# AD.net
KiCad netlist of a schematic drawn in Altium Designer
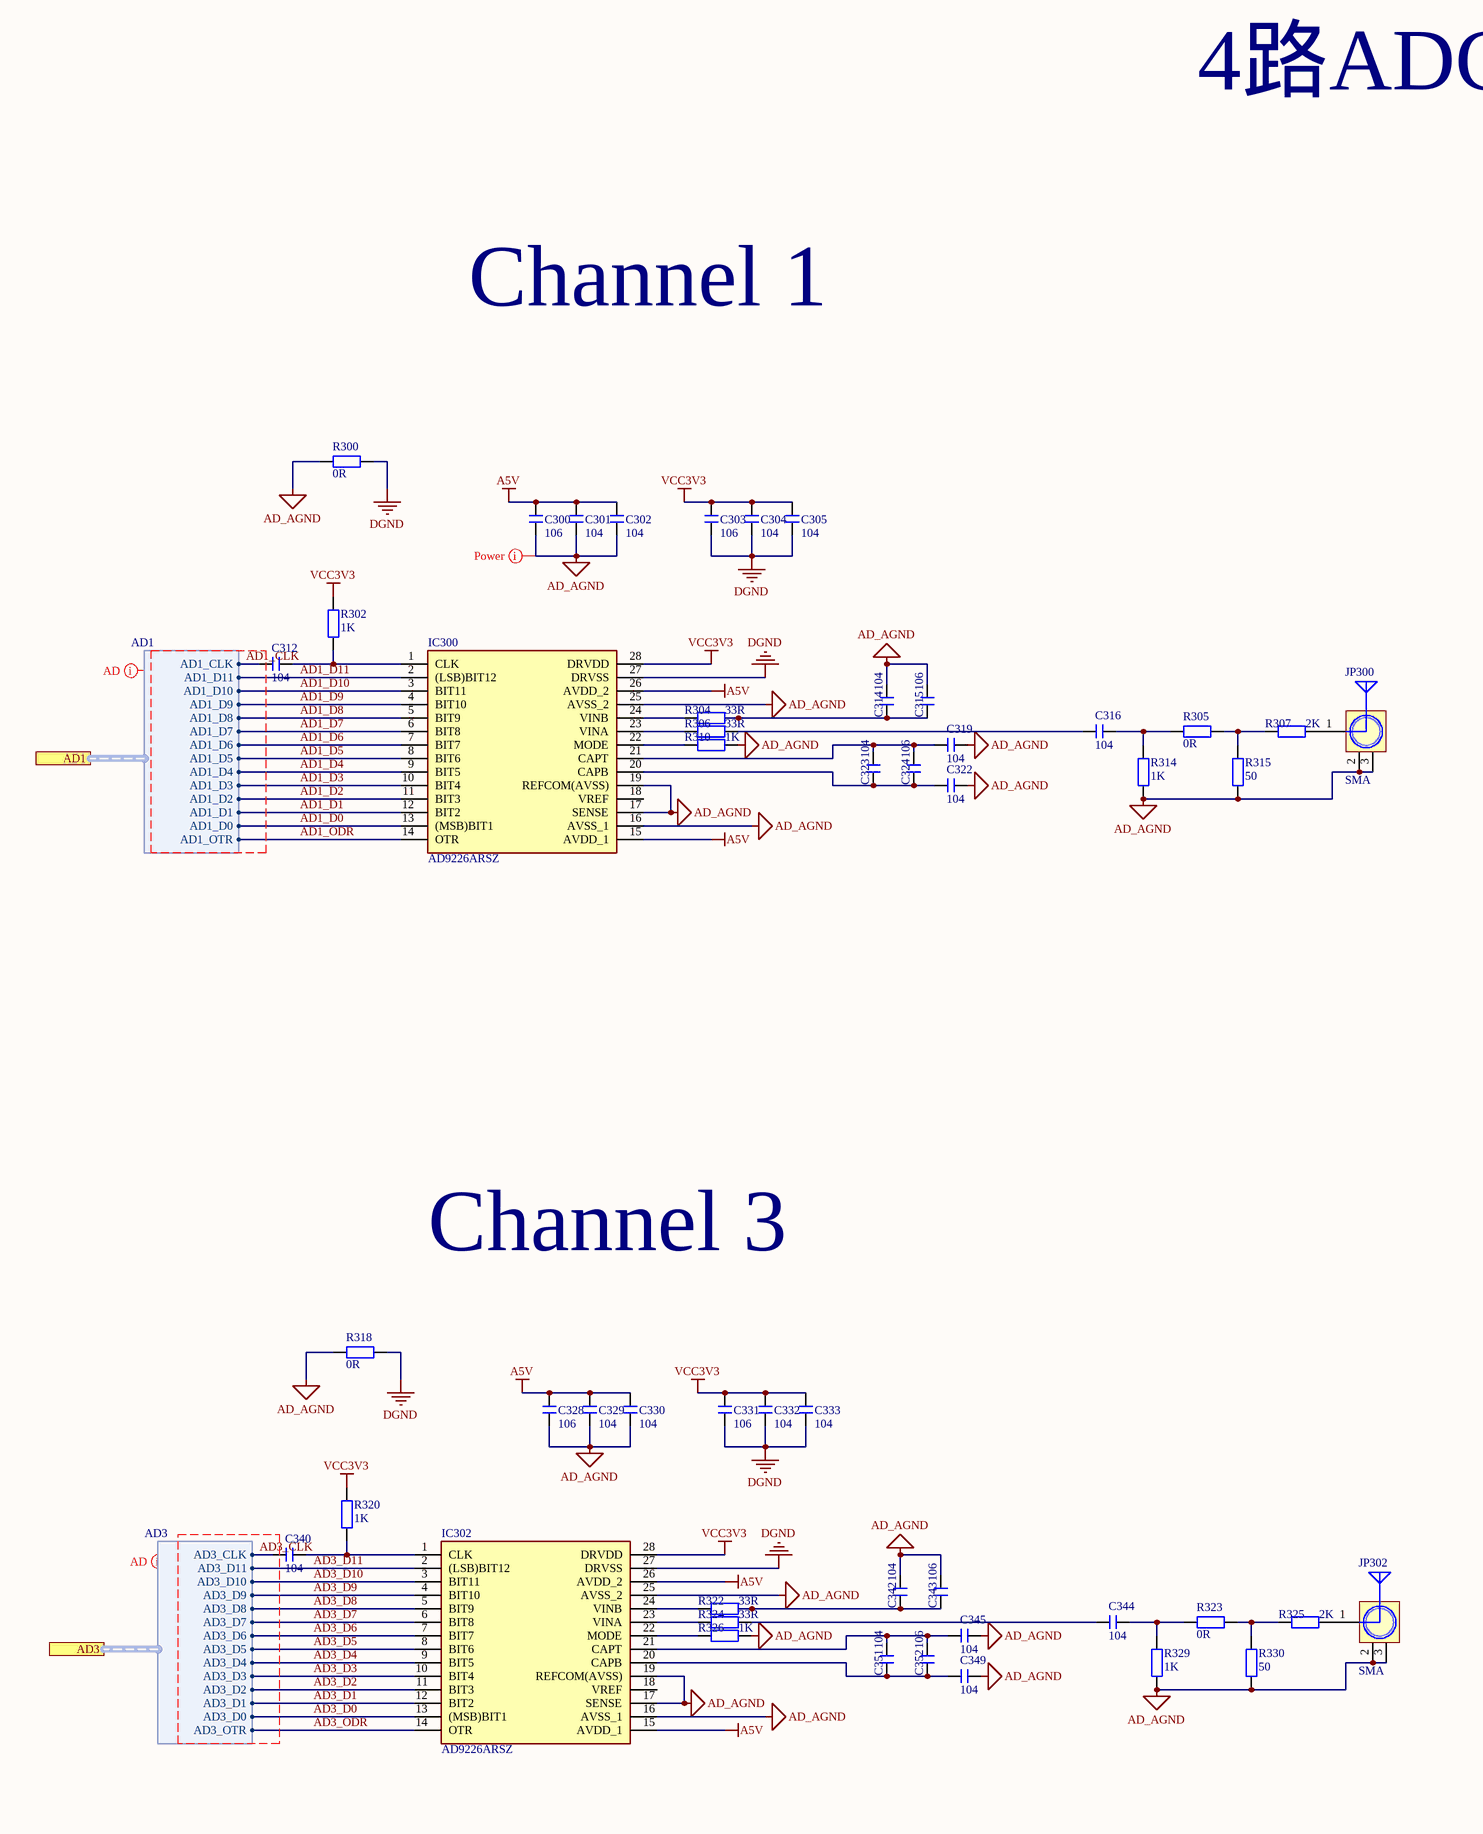
[diagram p0: AD.SchDoc, left]
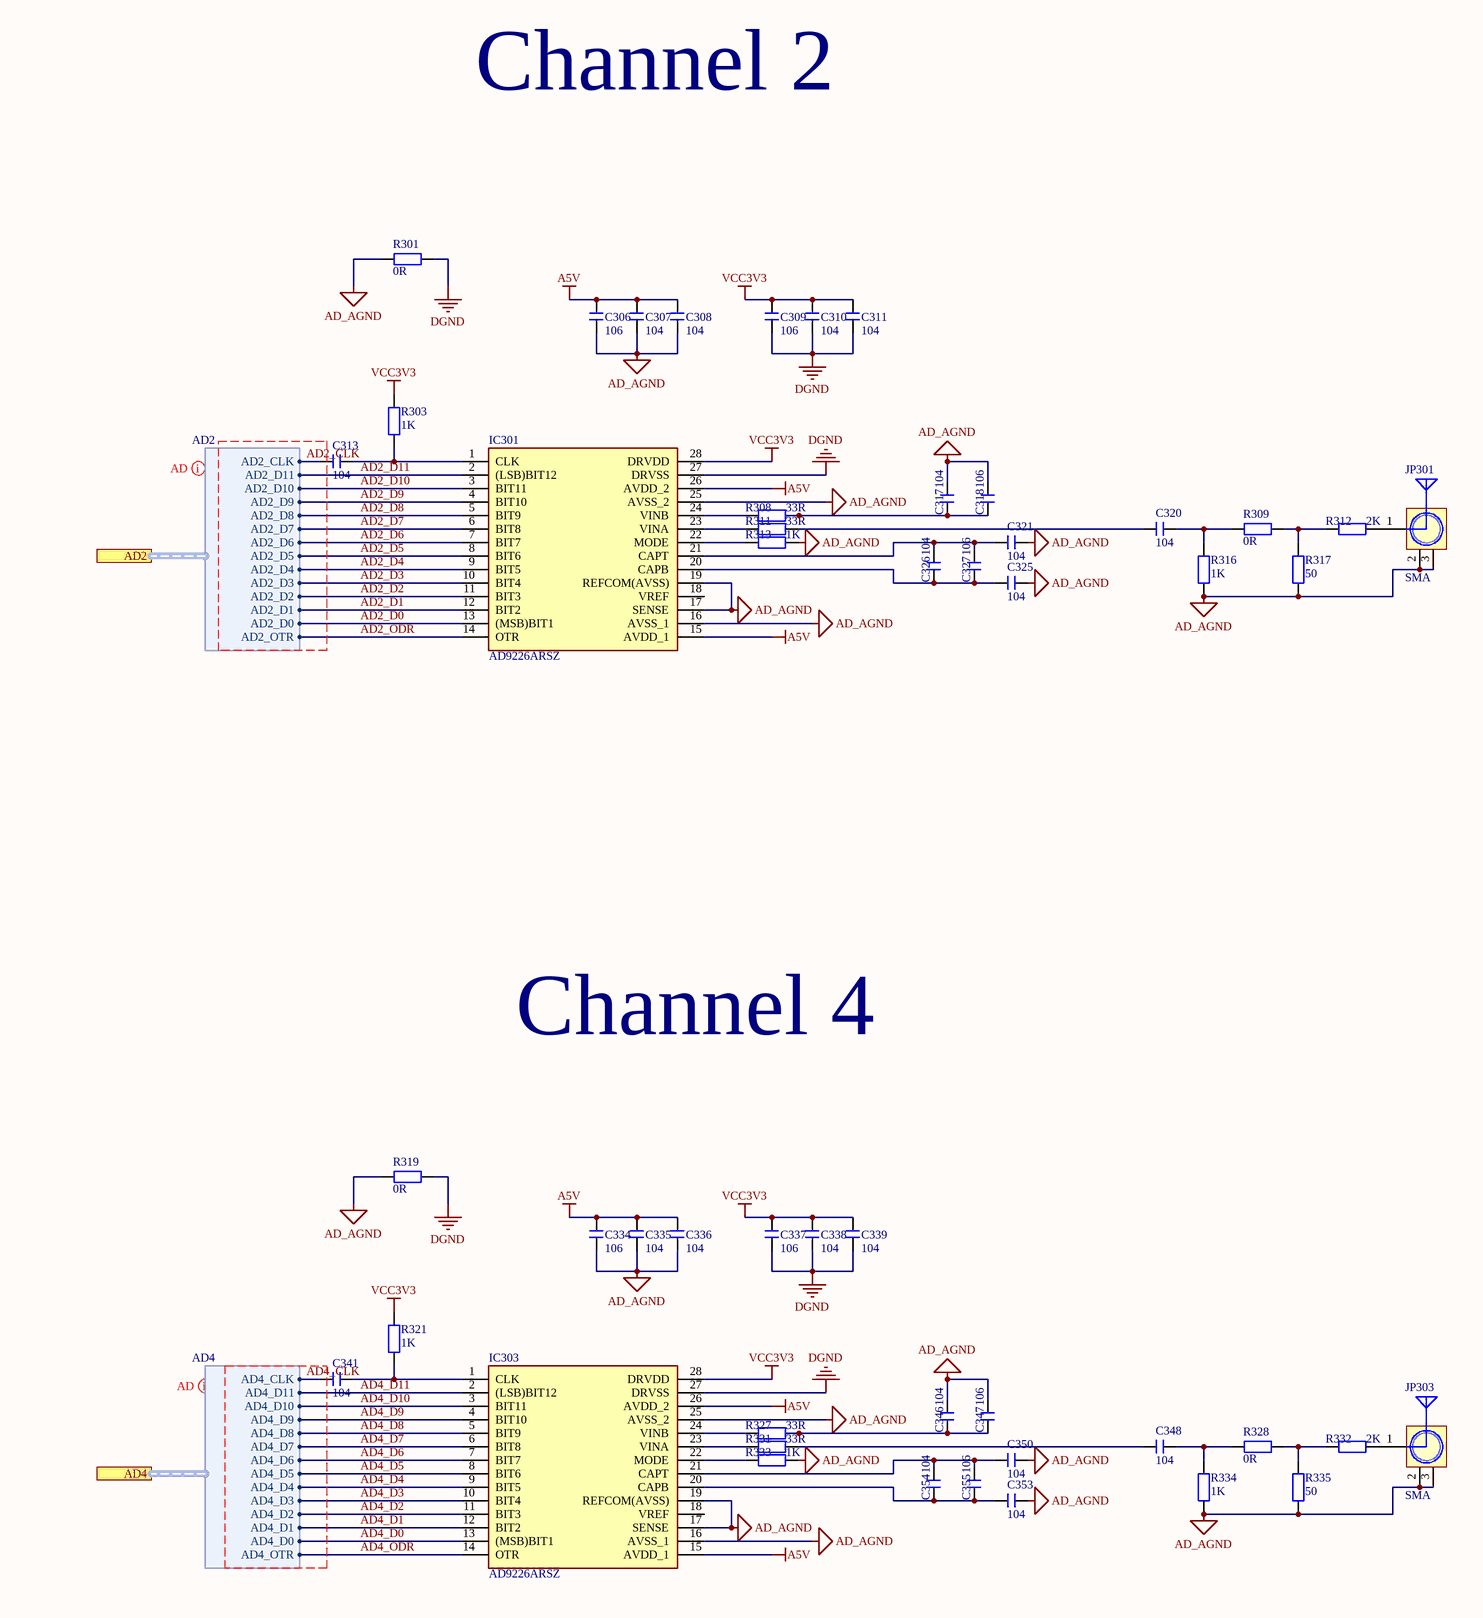
[diagram p1: AD.SchDoc, right]

(export (version "E")
  (design (tool "Eeschema 10.0.6"))
  (components
    (comp (ref "C300")
      (value "106")
      (footprint "C 0402_M")
      (description "无极性贴片电容")
      (fields (field (name "版权归属") "源创客"))
      (libsource (lib "3.1   - 电阻-电容-电感") (part "C"))
    )
    (comp (ref "C301")
      (value "104")
      (footprint "C 0402_M")
      (description "无极性贴片电容")
      (fields (field (name "版权归属") "源创客"))
      (libsource (lib "3.1   - 电阻-电容-电感") (part "C"))
    )
    (comp (ref "C302")
      (value "104")
      (footprint "C 0402_M")
      (description "无极性贴片电容")
      (fields (field (name "版权归属") "源创客"))
      (libsource (lib "3.1   - 电阻-电容-电感") (part "C"))
    )
    (comp (ref "C303")
      (value "106")
      (footprint "C 0402_M")
      (description "无极性贴片电容")
      (fields (field (name "版权归属") "源创客"))
      (libsource (lib "3.1   - 电阻-电容-电感") (part "C"))
    )
    (comp (ref "C304")
      (value "104")
      (footprint "C 0402_M")
      (description "无极性贴片电容")
      (fields (field (name "版权归属") "源创客"))
      (libsource (lib "3.1   - 电阻-电容-电感") (part "C"))
    )
    (comp (ref "C305")
      (value "104")
      (footprint "C 0402_M")
      (description "无极性贴片电容")
      (fields (field (name "版权归属") "源创客"))
      (libsource (lib "3.1   - 电阻-电容-电感") (part "C"))
    )
    (comp (ref "C306")
      (value "106")
      (footprint "C 0402_M")
      (description "无极性贴片电容")
      (fields (field (name "版权归属") "源创客"))
      (libsource (lib "3.1   - 电阻-电容-电感") (part "C"))
    )
    (comp (ref "C307")
      (value "104")
      (footprint "C 0402_M")
      (description "无极性贴片电容")
      (fields (field (name "版权归属") "源创客"))
      (libsource (lib "3.1   - 电阻-电容-电感") (part "C"))
    )
    (comp (ref "C308")
      (value "104")
      (footprint "C 0402_M")
      (description "无极性贴片电容")
      (fields (field (name "版权归属") "源创客"))
      (libsource (lib "3.1   - 电阻-电容-电感") (part "C"))
    )
    (comp (ref "C309")
      (value "106")
      (footprint "C 0402_M")
      (description "无极性贴片电容")
      (fields (field (name "版权归属") "源创客"))
      (libsource (lib "3.1   - 电阻-电容-电感") (part "C"))
    )
    (comp (ref "C310")
      (value "104")
      (footprint "C 0402_M")
      (description "无极性贴片电容")
      (fields (field (name "版权归属") "源创客"))
      (libsource (lib "3.1   - 电阻-电容-电感") (part "C"))
    )
    (comp (ref "C311")
      (value "104")
      (footprint "C 0402_M")
      (description "无极性贴片电容")
      (fields (field (name "版权归属") "源创客"))
      (libsource (lib "3.1   - 电阻-电容-电感") (part "C"))
    )
    (comp (ref "C312")
      (value "104")
      (footprint "C 0402_M")
      (description "无极性贴片电容")
      (fields (field (name "版权归属") "源创客"))
      (libsource (lib "3.1   - 电阻-电容-电感") (part "C"))
    )
    (comp (ref "C313")
      (value "104")
      (footprint "C 0402_M")
      (description "无极性贴片电容")
      (fields (field (name "版权归属") "源创客"))
      (libsource (lib "3.1   - 电阻-电容-电感") (part "C"))
    )
    (comp (ref "C314")
      (value "104")
      (footprint "C 0402_M")
      (description "无极性贴片电容")
      (fields (field (name "版权归属") "源创客"))
      (libsource (lib "3.1   - 电阻-电容-电感") (part "C"))
    )
    (comp (ref "C315")
      (value "106")
      (footprint "C 0402_M")
      (description "无极性贴片电容")
      (fields (field (name "版权归属") "源创客"))
      (libsource (lib "3.1   - 电阻-电容-电感") (part "C"))
    )
    (comp (ref "C316")
      (value "104")
      (footprint "C 0402_M")
      (description "无极性贴片电容")
      (fields (field (name "版权归属") "源创客"))
      (libsource (lib "3.1   - 电阻-电容-电感") (part "C"))
    )
    (comp (ref "C317")
      (value "104")
      (footprint "C 0402_M")
      (description "无极性贴片电容")
      (fields (field (name "版权归属") "源创客"))
      (libsource (lib "3.1   - 电阻-电容-电感") (part "C"))
    )
    (comp (ref "C318")
      (value "106")
      (footprint "C 0402_M")
      (description "无极性贴片电容")
      (fields (field (name "版权归属") "源创客"))
      (libsource (lib "3.1   - 电阻-电容-电感") (part "C"))
    )
    (comp (ref "C319")
      (value "104")
      (footprint "C 0402_M")
      (description "无极性贴片电容")
      (fields (field (name "版权归属") "源创客"))
      (libsource (lib "3.1   - 电阻-电容-电感") (part "C"))
    )
    (comp (ref "C320")
      (value "104")
      (footprint "C 0402_M")
      (description "无极性贴片电容")
      (fields (field (name "版权归属") "源创客"))
      (libsource (lib "3.1   - 电阻-电容-电感") (part "C"))
    )
    (comp (ref "C321")
      (value "104")
      (footprint "C 0402_M")
      (description "无极性贴片电容")
      (fields (field (name "版权归属") "源创客"))
      (libsource (lib "3.1   - 电阻-电容-电感") (part "C"))
    )
    (comp (ref "C322")
      (value "104")
      (footprint "C 0402_M")
      (description "无极性贴片电容")
      (fields (field (name "版权归属") "源创客"))
      (libsource (lib "3.1   - 电阻-电容-电感") (part "C"))
    )
    (comp (ref "C323")
      (value "104")
      (footprint "C 0402_M")
      (description "无极性贴片电容")
      (fields (field (name "版权归属") "源创客"))
      (libsource (lib "3.1   - 电阻-电容-电感") (part "C"))
    )
    (comp (ref "C324")
      (value "106")
      (footprint "C 0402_M")
      (description "无极性贴片电容")
      (fields (field (name "版权归属") "源创客"))
      (libsource (lib "3.1   - 电阻-电容-电感") (part "C"))
    )
    (comp (ref "C325")
      (value "104")
      (footprint "C 0402_M")
      (description "无极性贴片电容")
      (fields (field (name "版权归属") "源创客"))
      (libsource (lib "3.1   - 电阻-电容-电感") (part "C"))
    )
    (comp (ref "C326")
      (value "104")
      (footprint "C 0402_M")
      (description "无极性贴片电容")
      (fields (field (name "版权归属") "源创客"))
      (libsource (lib "3.1   - 电阻-电容-电感") (part "C"))
    )
    (comp (ref "C327")
      (value "106")
      (footprint "C 0402_M")
      (description "无极性贴片电容")
      (fields (field (name "版权归属") "源创客"))
      (libsource (lib "3.1   - 电阻-电容-电感") (part "C"))
    )
    (comp (ref "C328")
      (value "106")
      (footprint "C 0402_M")
      (description "无极性贴片电容")
      (fields (field (name "版权归属") "源创客"))
      (libsource (lib "3.1   - 电阻-电容-电感") (part "C"))
    )
    (comp (ref "C329")
      (value "104")
      (footprint "C 0402_M")
      (description "无极性贴片电容")
      (fields (field (name "版权归属") "源创客"))
      (libsource (lib "3.1   - 电阻-电容-电感") (part "C"))
    )
    (comp (ref "C330")
      (value "104")
      (footprint "C 0402_M")
      (description "无极性贴片电容")
      (fields (field (name "版权归属") "源创客"))
      (libsource (lib "3.1   - 电阻-电容-电感") (part "C"))
    )
    (comp (ref "C331")
      (value "106")
      (footprint "C 0402_M")
      (description "无极性贴片电容")
      (fields (field (name "版权归属") "源创客"))
      (libsource (lib "3.1   - 电阻-电容-电感") (part "C"))
    )
    (comp (ref "C332")
      (value "104")
      (footprint "C 0402_M")
      (description "无极性贴片电容")
      (fields (field (name "版权归属") "源创客"))
      (libsource (lib "3.1   - 电阻-电容-电感") (part "C"))
    )
    (comp (ref "C333")
      (value "104")
      (footprint "C 0402_M")
      (description "无极性贴片电容")
      (fields (field (name "版权归属") "源创客"))
      (libsource (lib "3.1   - 电阻-电容-电感") (part "C"))
    )
    (comp (ref "C334")
      (value "106")
      (footprint "C 0402_M")
      (description "无极性贴片电容")
      (fields (field (name "版权归属") "源创客"))
      (libsource (lib "3.1   - 电阻-电容-电感") (part "C"))
    )
    (comp (ref "C335")
      (value "104")
      (footprint "C 0402_M")
      (description "无极性贴片电容")
      (fields (field (name "版权归属") "源创客"))
      (libsource (lib "3.1   - 电阻-电容-电感") (part "C"))
    )
    (comp (ref "C336")
      (value "104")
      (footprint "C 0402_M")
      (description "无极性贴片电容")
      (fields (field (name "版权归属") "源创客"))
      (libsource (lib "3.1   - 电阻-电容-电感") (part "C"))
    )
    (comp (ref "C337")
      (value "106")
      (footprint "C 0402_M")
      (description "无极性贴片电容")
      (fields (field (name "版权归属") "源创客"))
      (libsource (lib "3.1   - 电阻-电容-电感") (part "C"))
    )
    (comp (ref "C338")
      (value "104")
      (footprint "C 0402_M")
      (description "无极性贴片电容")
      (fields (field (name "版权归属") "源创客"))
      (libsource (lib "3.1   - 电阻-电容-电感") (part "C"))
    )
    (comp (ref "C339")
      (value "104")
      (footprint "C 0402_M")
      (description "无极性贴片电容")
      (fields (field (name "版权归属") "源创客"))
      (libsource (lib "3.1   - 电阻-电容-电感") (part "C"))
    )
    (comp (ref "C340")
      (value "104")
      (footprint "C 0402_M")
      (description "无极性贴片电容")
      (fields (field (name "版权归属") "源创客"))
      (libsource (lib "3.1   - 电阻-电容-电感") (part "C"))
    )
    (comp (ref "C341")
      (value "104")
      (footprint "C 0402_M")
      (description "无极性贴片电容")
      (fields (field (name "版权归属") "源创客"))
      (libsource (lib "3.1   - 电阻-电容-电感") (part "C"))
    )
    (comp (ref "C342")
      (value "104")
      (footprint "C 0402_M")
      (description "无极性贴片电容")
      (fields (field (name "版权归属") "源创客"))
      (libsource (lib "3.1   - 电阻-电容-电感") (part "C"))
    )
    (comp (ref "C343")
      (value "106")
      (footprint "C 0402_M")
      (description "无极性贴片电容")
      (fields (field (name "版权归属") "源创客"))
      (libsource (lib "3.1   - 电阻-电容-电感") (part "C"))
    )
    (comp (ref "C344")
      (value "104")
      (footprint "C 0402_M")
      (description "无极性贴片电容")
      (fields (field (name "版权归属") "源创客"))
      (libsource (lib "3.1   - 电阻-电容-电感") (part "C"))
    )
    (comp (ref "C345")
      (value "104")
      (footprint "C 0402_M")
      (description "无极性贴片电容")
      (fields (field (name "版权归属") "源创客"))
      (libsource (lib "3.1   - 电阻-电容-电感") (part "C"))
    )
    (comp (ref "C346")
      (value "104")
      (footprint "C 0402_M")
      (description "无极性贴片电容")
      (fields (field (name "版权归属") "源创客"))
      (libsource (lib "3.1   - 电阻-电容-电感") (part "C"))
    )
    (comp (ref "C347")
      (value "106")
      (footprint "C 0402_M")
      (description "无极性贴片电容")
      (fields (field (name "版权归属") "源创客"))
      (libsource (lib "3.1   - 电阻-电容-电感") (part "C"))
    )
    (comp (ref "C348")
      (value "104")
      (footprint "C 0402_M")
      (description "无极性贴片电容")
      (fields (field (name "版权归属") "源创客"))
      (libsource (lib "3.1   - 电阻-电容-电感") (part "C"))
    )
    (comp (ref "C349")
      (value "104")
      (footprint "C 0402_M")
      (description "无极性贴片电容")
      (fields (field (name "版权归属") "源创客"))
      (libsource (lib "3.1   - 电阻-电容-电感") (part "C"))
    )
    (comp (ref "C350")
      (value "104")
      (footprint "C 0402_M")
      (description "无极性贴片电容")
      (fields (field (name "版权归属") "源创客"))
      (libsource (lib "3.1   - 电阻-电容-电感") (part "C"))
    )
    (comp (ref "C351")
      (value "104")
      (footprint "C 0402_M")
      (description "无极性贴片电容")
      (fields (field (name "版权归属") "源创客"))
      (libsource (lib "3.1   - 电阻-电容-电感") (part "C"))
    )
    (comp (ref "C352")
      (value "106")
      (footprint "C 0402_M")
      (description "无极性贴片电容")
      (fields (field (name "版权归属") "源创客"))
      (libsource (lib "3.1   - 电阻-电容-电感") (part "C"))
    )
    (comp (ref "C353")
      (value "104")
      (footprint "C 0402_M")
      (description "无极性贴片电容")
      (fields (field (name "版权归属") "源创客"))
      (libsource (lib "3.1   - 电阻-电容-电感") (part "C"))
    )
    (comp (ref "C354")
      (value "104")
      (footprint "C 0402_M")
      (description "无极性贴片电容")
      (fields (field (name "版权归属") "源创客"))
      (libsource (lib "3.1   - 电阻-电容-电感") (part "C"))
    )
    (comp (ref "C355")
      (value "106")
      (footprint "C 0402_M")
      (description "无极性贴片电容")
      (fields (field (name "版权归属") "源创客"))
      (libsource (lib "3.1   - 电阻-电容-电感") (part "C"))
    )
    (comp (ref "IC300")
      (value "AD9226ARSZ")
      (footprint "PcbLib1:SOP65P777X198-28N")
      (description "Integrated Circuit")
      (fields (field (name "MOUSER PART NUMBER") "584-AD9226ARSZ") (field (name "RS PART NUMBER") "4973407P"))
      (libsource (lib "altium-import") (part "root_0_AD9226ARSZ_"))
    )
    (comp (ref "IC301")
      (value "AD9226ARSZ")
      (footprint "PcbLib1:SOP65P777X198-28N")
      (description "Integrated Circuit")
      (fields (field (name "MOUSER PART NUMBER") "584-AD9226ARSZ") (field (name "RS PART NUMBER") "4973407P"))
      (libsource (lib "altium-import") (part "root_0_AD9226ARSZ_"))
    )
    (comp (ref "IC302")
      (value "AD9226ARSZ")
      (footprint "PcbLib1:SOP65P777X198-28N")
      (description "Integrated Circuit")
      (fields (field (name "MOUSER PART NUMBER") "584-AD9226ARSZ") (field (name "RS PART NUMBER") "4973407P"))
      (libsource (lib "altium-import") (part "root_0_AD9226ARSZ_"))
    )
    (comp (ref "IC303")
      (value "AD9226ARSZ")
      (footprint "PcbLib1:SOP65P777X198-28N")
      (description "Integrated Circuit")
      (fields (field (name "MOUSER PART NUMBER") "584-AD9226ARSZ") (field (name "RS PART NUMBER") "4973407P"))
      (libsource (lib "altium-import") (part "root_0_AD9226ARSZ_"))
    )
    (comp (ref "JP300")
      (value "SMA")
      (footprint "SMA_FR")
      (description "SMA-2.4G射频天线接口")
      (fields (field (name "版权归属") "源创客"))
      (libsource (lib "4.1   - 接口类") (part "SMA"))
    )
    (comp (ref "JP301")
      (value "SMA")
      (footprint "SMA_FR")
      (description "SMA-2.4G射频天线接口")
      (fields (field (name "版权归属") "源创客"))
      (libsource (lib "4.1   - 接口类") (part "SMA"))
    )
    (comp (ref "JP302")
      (value "SMA")
      (footprint "SMA_FR")
      (description "SMA-2.4G射频天线接口")
      (fields (field (name "版权归属") "源创客"))
      (libsource (lib "4.1   - 接口类") (part "SMA"))
    )
    (comp (ref "JP303")
      (value "SMA")
      (footprint "SMA_FR")
      (description "SMA-2.4G射频天线接口")
      (fields (field (name "版权归属") "源创客"))
      (libsource (lib "4.1   - 接口类") (part "SMA"))
    )
    (comp (ref "R300")
      (value "0R")
      (footprint "R 0402_M")
      (description "贴片电阻")
      (fields (field (name "版权归属") "源创客"))
      (libsource (lib "3.1   - 电阻-电容-电感") (part "R"))
    )
    (comp (ref "R301")
      (value "0R")
      (footprint "R 0402_M")
      (description "贴片电阻")
      (fields (field (name "版权归属") "源创客"))
      (libsource (lib "3.1   - 电阻-电容-电感") (part "R"))
    )
    (comp (ref "R302")
      (value "1K")
      (footprint "R 0402_M")
      (description "贴片电阻")
      (fields (field (name "版权归属") "源创客"))
      (libsource (lib "3.1   - 电阻-电容-电感") (part "R"))
    )
    (comp (ref "R303")
      (value "1K")
      (footprint "R 0402_M")
      (description "贴片电阻")
      (fields (field (name "版权归属") "源创客"))
      (libsource (lib "3.1   - 电阻-电容-电感") (part "R"))
    )
    (comp (ref "R304")
      (value "33R")
      (footprint "R 0402_M")
      (description "贴片电阻")
      (fields (field (name "版权归属") "源创客"))
      (libsource (lib "3.1   - 电阻-电容-电感") (part "R"))
    )
    (comp (ref "R305")
      (value "0R")
      (footprint "R 0402_M")
      (description "贴片电阻")
      (fields (field (name "版权归属") "源创客"))
      (libsource (lib "3.1   - 电阻-电容-电感") (part "R"))
    )
    (comp (ref "R306")
      (value "33R")
      (footprint "R 0402_M")
      (description "贴片电阻")
      (fields (field (name "版权归属") "源创客"))
      (libsource (lib "3.1   - 电阻-电容-电感") (part "R"))
    )
    (comp (ref "R307")
      (value "2K")
      (footprint "R 0402_M")
      (description "贴片电阻")
      (fields (field (name "版权归属") "源创客"))
      (libsource (lib "3.1   - 电阻-电容-电感") (part "R"))
    )
    (comp (ref "R308")
      (value "33R")
      (footprint "R 0402_M")
      (description "贴片电阻")
      (fields (field (name "版权归属") "源创客"))
      (libsource (lib "3.1   - 电阻-电容-电感") (part "R"))
    )
    (comp (ref "R309")
      (value "0R")
      (footprint "R 0402_M")
      (description "贴片电阻")
      (fields (field (name "版权归属") "源创客"))
      (libsource (lib "3.1   - 电阻-电容-电感") (part "R"))
    )
    (comp (ref "R310")
      (value "1K")
      (footprint "R 0402_M")
      (description "贴片电阻")
      (fields (field (name "版权归属") "源创客"))
      (libsource (lib "3.1   - 电阻-电容-电感") (part "R"))
    )
    (comp (ref "R311")
      (value "33R")
      (footprint "R 0402_M")
      (description "贴片电阻")
      (fields (field (name "版权归属") "源创客"))
      (libsource (lib "3.1   - 电阻-电容-电感") (part "R"))
    )
    (comp (ref "R312")
      (value "2K")
      (footprint "R 0402_M")
      (description "贴片电阻")
      (fields (field (name "版权归属") "源创客"))
      (libsource (lib "3.1   - 电阻-电容-电感") (part "R"))
    )
    (comp (ref "R313")
      (value "1K")
      (footprint "R 0402_M")
      (description "贴片电阻")
      (fields (field (name "版权归属") "源创客"))
      (libsource (lib "3.1   - 电阻-电容-电感") (part "R"))
    )
    (comp (ref "R314")
      (value "1K")
      (footprint "R 0402_M")
      (description "贴片电阻")
      (fields (field (name "版权归属") "源创客"))
      (libsource (lib "3.1   - 电阻-电容-电感") (part "R"))
    )
    (comp (ref "R315")
      (value "50")
      (footprint "R 0402_M")
      (description "贴片电阻")
      (fields (field (name "版权归属") "源创客"))
      (libsource (lib "3.1   - 电阻-电容-电感") (part "R"))
    )
    (comp (ref "R316")
      (value "1K")
      (footprint "R 0402_M")
      (description "贴片电阻")
      (fields (field (name "版权归属") "源创客"))
      (libsource (lib "3.1   - 电阻-电容-电感") (part "R"))
    )
    (comp (ref "R317")
      (value "50")
      (footprint "R 0402_M")
      (description "贴片电阻")
      (fields (field (name "版权归属") "源创客"))
      (libsource (lib "3.1   - 电阻-电容-电感") (part "R"))
    )
    (comp (ref "R318")
      (value "0R")
      (footprint "R 0402_M")
      (description "贴片电阻")
      (fields (field (name "版权归属") "源创客"))
      (libsource (lib "3.1   - 电阻-电容-电感") (part "R"))
    )
    (comp (ref "R319")
      (value "0R")
      (footprint "R 0402_M")
      (description "贴片电阻")
      (fields (field (name "版权归属") "源创客"))
      (libsource (lib "3.1   - 电阻-电容-电感") (part "R"))
    )
    (comp (ref "R320")
      (value "1K")
      (footprint "R 0402_M")
      (description "贴片电阻")
      (fields (field (name "版权归属") "源创客"))
      (libsource (lib "3.1   - 电阻-电容-电感") (part "R"))
    )
    (comp (ref "R321")
      (value "1K")
      (footprint "R 0402_M")
      (description "贴片电阻")
      (fields (field (name "版权归属") "源创客"))
      (libsource (lib "3.1   - 电阻-电容-电感") (part "R"))
    )
    (comp (ref "R322")
      (value "33R")
      (footprint "R 0402_M")
      (description "贴片电阻")
      (fields (field (name "版权归属") "源创客"))
      (libsource (lib "3.1   - 电阻-电容-电感") (part "R"))
    )
    (comp (ref "R323")
      (value "0R")
      (footprint "R 0402_M")
      (description "贴片电阻")
      (fields (field (name "版权归属") "源创客"))
      (libsource (lib "3.1   - 电阻-电容-电感") (part "R"))
    )
    (comp (ref "R324")
      (value "33R")
      (footprint "R 0402_M")
      (description "贴片电阻")
      (fields (field (name "版权归属") "源创客"))
      (libsource (lib "3.1   - 电阻-电容-电感") (part "R"))
    )
    (comp (ref "R325")
      (value "2K")
      (footprint "R 0402_M")
      (description "贴片电阻")
      (fields (field (name "版权归属") "源创客"))
      (libsource (lib "3.1   - 电阻-电容-电感") (part "R"))
    )
    (comp (ref "R326")
      (value "1K")
      (footprint "R 0402_M")
      (description "贴片电阻")
      (fields (field (name "版权归属") "源创客"))
      (libsource (lib "3.1   - 电阻-电容-电感") (part "R"))
    )
    (comp (ref "R327")
      (value "33R")
      (footprint "R 0402_M")
      (description "贴片电阻")
      (fields (field (name "版权归属") "源创客"))
      (libsource (lib "3.1   - 电阻-电容-电感") (part "R"))
    )
    (comp (ref "R328")
      (value "0R")
      (footprint "R 0402_M")
      (description "贴片电阻")
      (fields (field (name "版权归属") "源创客"))
      (libsource (lib "3.1   - 电阻-电容-电感") (part "R"))
    )
    (comp (ref "R329")
      (value "1K")
      (footprint "R 0402_M")
      (description "贴片电阻")
      (fields (field (name "版权归属") "源创客"))
      (libsource (lib "3.1   - 电阻-电容-电感") (part "R"))
    )
    (comp (ref "R330")
      (value "50")
      (footprint "R 0402_M")
      (description "贴片电阻")
      (fields (field (name "版权归属") "源创客"))
      (libsource (lib "3.1   - 电阻-电容-电感") (part "R"))
    )
    (comp (ref "R331")
      (value "33R")
      (footprint "R 0402_M")
      (description "贴片电阻")
      (fields (field (name "版权归属") "源创客"))
      (libsource (lib "3.1   - 电阻-电容-电感") (part "R"))
    )
    (comp (ref "R332")
      (value "2K")
      (footprint "R 0402_M")
      (description "贴片电阻")
      (fields (field (name "版权归属") "源创客"))
      (libsource (lib "3.1   - 电阻-电容-电感") (part "R"))
    )
    (comp (ref "R333")
      (value "1K")
      (footprint "R 0402_M")
      (description "贴片电阻")
      (fields (field (name "版权归属") "源创客"))
      (libsource (lib "3.1   - 电阻-电容-电感") (part "R"))
    )
    (comp (ref "R334")
      (value "1K")
      (footprint "R 0402_M")
      (description "贴片电阻")
      (fields (field (name "版权归属") "源创客"))
      (libsource (lib "3.1   - 电阻-电容-电感") (part "R"))
    )
    (comp (ref "R335")
      (value "50")
      (footprint "R 0402_M")
      (description "贴片电阻")
      (fields (field (name "版权归属") "源创客"))
      (libsource (lib "3.1   - 电阻-电容-电感") (part "R"))
    )
  )
  (nets
    (net (code "5") (name "/AD1_CLK") (class "Default")
      (node (ref "C312") (pin "2") (pinfunction "2_2") (pintype "passive"))
    )
    (net (code "6") (name "/AD1_D0") (class "Default")
      (node (ref "IC300") (pin "13") (pinfunction "(MSB)BIT1_13") (pintype "passive"))
    )
    (net (code "7") (name "/AD1_D1") (class "Default")
      (node (ref "IC300") (pin "12") (pinfunction "BIT2_12") (pintype "passive"))
    )
    (net (code "8") (name "/AD1_D2") (class "Default")
      (node (ref "IC300") (pin "11") (pinfunction "BIT3_11") (pintype "passive"))
    )
    (net (code "9") (name "/AD1_D3") (class "Default")
      (node (ref "IC300") (pin "10") (pinfunction "BIT4_10") (pintype "passive"))
    )
    (net (code "10") (name "/AD1_D4") (class "Default")
      (node (ref "IC300") (pin "9") (pinfunction "BIT5_9") (pintype "passive"))
    )
    (net (code "11") (name "/AD1_D5") (class "Default")
      (node (ref "IC300") (pin "8") (pinfunction "BIT6_8") (pintype "passive"))
    )
    (net (code "12") (name "/AD1_D6") (class "Default")
      (node (ref "IC300") (pin "7") (pinfunction "BIT7_7") (pintype "passive"))
    )
    (net (code "13") (name "/AD1_D7") (class "Default")
      (node (ref "IC300") (pin "6") (pinfunction "BIT8_6") (pintype "passive"))
    )
    (net (code "14") (name "/AD1_D8") (class "Default")
      (node (ref "IC300") (pin "5") (pinfunction "BIT9_5") (pintype "passive"))
    )
    (net (code "15") (name "/AD1_D9") (class "Default")
      (node (ref "IC300") (pin "4") (pinfunction "BIT10_4") (pintype "passive"))
    )
    (net (code "16") (name "/AD1_D10") (class "Default")
      (node (ref "IC300") (pin "3") (pinfunction "BIT11_3") (pintype "passive"))
    )
    (net (code "17") (name "/AD1_D11") (class "Default")
      (node (ref "IC300") (pin "2") (pinfunction "(LSB)BIT12_2") (pintype "passive"))
    )
    (net (code "18") (name "/AD1_ODR") (class "Default")
      (node (ref "IC300") (pin "14") (pinfunction "OTR_14") (pintype "passive"))
    )
    (net (code "19") (name "/AD2_CLK") (class "Default")
      (node (ref "C313") (pin "2") (pinfunction "2_2") (pintype "passive"))
    )
    (net (code "20") (name "/AD2_D0") (class "Default")
      (node (ref "IC301") (pin "13") (pinfunction "(MSB)BIT1_13") (pintype "passive"))
    )
    (net (code "21") (name "/AD2_D1") (class "Default")
      (node (ref "IC301") (pin "12") (pinfunction "BIT2_12") (pintype "passive"))
    )
    (net (code "22") (name "/AD2_D2") (class "Default")
      (node (ref "IC301") (pin "11") (pinfunction "BIT3_11") (pintype "passive"))
    )
    (net (code "23") (name "/AD2_D3") (class "Default")
      (node (ref "IC301") (pin "10") (pinfunction "BIT4_10") (pintype "passive"))
    )
    (net (code "24") (name "/AD2_D4") (class "Default")
      (node (ref "IC301") (pin "9") (pinfunction "BIT5_9") (pintype "passive"))
    )
    (net (code "25") (name "/AD2_D5") (class "Default")
      (node (ref "IC301") (pin "8") (pinfunction "BIT6_8") (pintype "passive"))
    )
    (net (code "26") (name "/AD2_D6") (class "Default")
      (node (ref "IC301") (pin "7") (pinfunction "BIT7_7") (pintype "passive"))
    )
    (net (code "27") (name "/AD2_D7") (class "Default")
      (node (ref "IC301") (pin "6") (pinfunction "BIT8_6") (pintype "passive"))
    )
    (net (code "28") (name "/AD2_D8") (class "Default")
      (node (ref "IC301") (pin "5") (pinfunction "BIT9_5") (pintype "passive"))
    )
    (net (code "29") (name "/AD2_D9") (class "Default")
      (node (ref "IC301") (pin "4") (pinfunction "BIT10_4") (pintype "passive"))
    )
    (net (code "30") (name "/AD2_D10") (class "Default")
      (node (ref "IC301") (pin "3") (pinfunction "BIT11_3") (pintype "passive"))
    )
    (net (code "31") (name "/AD2_D11") (class "Default")
      (node (ref "IC301") (pin "2") (pinfunction "(LSB)BIT12_2") (pintype "passive"))
    )
    (net (code "32") (name "/AD2_ODR") (class "Default")
      (node (ref "IC301") (pin "14") (pinfunction "OTR_14") (pintype "passive"))
    )
    (net (code "33") (name "/AD3_CLK") (class "Default")
      (node (ref "C340") (pin "2") (pinfunction "2_2") (pintype "passive"))
    )
    (net (code "34") (name "/AD3_D0") (class "Default")
      (node (ref "IC302") (pin "13") (pinfunction "(MSB)BIT1_13") (pintype "passive"))
    )
    (net (code "35") (name "/AD3_D1") (class "Default")
      (node (ref "IC302") (pin "12") (pinfunction "BIT2_12") (pintype "passive"))
    )
    (net (code "36") (name "/AD3_D2") (class "Default")
      (node (ref "IC302") (pin "11") (pinfunction "BIT3_11") (pintype "passive"))
    )
    (net (code "37") (name "/AD3_D3") (class "Default")
      (node (ref "IC302") (pin "10") (pinfunction "BIT4_10") (pintype "passive"))
    )
    (net (code "38") (name "/AD3_D4") (class "Default")
      (node (ref "IC302") (pin "9") (pinfunction "BIT5_9") (pintype "passive"))
    )
    (net (code "39") (name "/AD3_D5") (class "Default")
      (node (ref "IC302") (pin "8") (pinfunction "BIT6_8") (pintype "passive"))
    )
    (net (code "40") (name "/AD3_D6") (class "Default")
      (node (ref "IC302") (pin "7") (pinfunction "BIT7_7") (pintype "passive"))
    )
    (net (code "41") (name "/AD3_D7") (class "Default")
      (node (ref "IC302") (pin "6") (pinfunction "BIT8_6") (pintype "passive"))
    )
    (net (code "42") (name "/AD3_D8") (class "Default")
      (node (ref "IC302") (pin "5") (pinfunction "BIT9_5") (pintype "passive"))
    )
    (net (code "43") (name "/AD3_D9") (class "Default")
      (node (ref "IC302") (pin "4") (pinfunction "BIT10_4") (pintype "passive"))
    )
    (net (code "44") (name "/AD3_D10") (class "Default")
      (node (ref "IC302") (pin "3") (pinfunction "BIT11_3") (pintype "passive"))
    )
    (net (code "45") (name "/AD3_D11") (class "Default")
      (node (ref "IC302") (pin "2") (pinfunction "(LSB)BIT12_2") (pintype "passive"))
    )
    (net (code "46") (name "/AD3_ODR") (class "Default")
      (node (ref "IC302") (pin "14") (pinfunction "OTR_14") (pintype "passive"))
    )
    (net (code "47") (name "/AD4_CLK") (class "Default")
      (node (ref "C341") (pin "2") (pinfunction "2_2") (pintype "passive"))
    )
    (net (code "48") (name "/AD4_D0") (class "Default")
      (node (ref "IC303") (pin "13") (pinfunction "(MSB)BIT1_13") (pintype "passive"))
    )
    (net (code "49") (name "/AD4_D1") (class "Default")
      (node (ref "IC303") (pin "12") (pinfunction "BIT2_12") (pintype "passive"))
    )
    (net (code "50") (name "/AD4_D2") (class "Default")
      (node (ref "IC303") (pin "11") (pinfunction "BIT3_11") (pintype "passive"))
    )
    (net (code "51") (name "/AD4_D3") (class "Default")
      (node (ref "IC303") (pin "10") (pinfunction "BIT4_10") (pintype "passive"))
    )
    (net (code "52") (name "/AD4_D4") (class "Default")
      (node (ref "IC303") (pin "9") (pinfunction "BIT5_9") (pintype "passive"))
    )
    (net (code "53") (name "/AD4_D5") (class "Default")
      (node (ref "IC303") (pin "8") (pinfunction "BIT6_8") (pintype "passive"))
    )
    (net (code "54") (name "/AD4_D6") (class "Default")
      (node (ref "IC303") (pin "7") (pinfunction "BIT7_7") (pintype "passive"))
    )
    (net (code "55") (name "/AD4_D7") (class "Default")
      (node (ref "IC303") (pin "6") (pinfunction "BIT8_6") (pintype "passive"))
    )
    (net (code "56") (name "/AD4_D8") (class "Default")
      (node (ref "IC303") (pin "5") (pinfunction "BIT9_5") (pintype "passive"))
    )
    (net (code "57") (name "/AD4_D9") (class "Default")
      (node (ref "IC303") (pin "4") (pinfunction "BIT10_4") (pintype "passive"))
    )
    (net (code "58") (name "/AD4_D10") (class "Default")
      (node (ref "IC303") (pin "3") (pinfunction "BIT11_3") (pintype "passive"))
    )
    (net (code "59") (name "/AD4_D11") (class "Default")
      (node (ref "IC303") (pin "2") (pinfunction "(LSB)BIT12_2") (pintype "passive"))
    )
    (net (code "60") (name "/AD4_ODR") (class "Default")
      (node (ref "IC303") (pin "14") (pinfunction "OTR_14") (pintype "passive"))
    )
    (net (code "65") (name "A5V") (class "Default")
      (node (ref "C300") (pin "1") (pinfunction "1_1") (pintype "passive"))
      (node (ref "C301") (pin "1") (pinfunction "1_1") (pintype "passive"))
      (node (ref "C302") (pin "1") (pinfunction "1_1") (pintype "passive"))
      (node (ref "C306") (pin "1") (pinfunction "1_1") (pintype "passive"))
      (node (ref "C307") (pin "1") (pinfunction "1_1") (pintype "passive"))
      (node (ref "C308") (pin "1") (pinfunction "1_1") (pintype "passive"))
      (node (ref "C328") (pin "1") (pinfunction "1_1") (pintype "passive"))
      (node (ref "C329") (pin "1") (pinfunction "1_1") (pintype "passive"))
      (node (ref "C330") (pin "1") (pinfunction "1_1") (pintype "passive"))
      (node (ref "C334") (pin "1") (pinfunction "1_1") (pintype "passive"))
      (node (ref "C335") (pin "1") (pinfunction "1_1") (pintype "passive"))
      (node (ref "C336") (pin "1") (pinfunction "1_1") (pintype "passive"))
      (node (ref "IC300") (pin "15") (pinfunction "AVDD_1_15") (pintype "passive"))
      (node (ref "IC300") (pin "26") (pinfunction "AVDD_2_26") (pintype "passive"))
      (node (ref "IC301") (pin "15") (pinfunction "AVDD_1_15") (pintype "passive"))
      (node (ref "IC301") (pin "26") (pinfunction "AVDD_2_26") (pintype "passive"))
      (node (ref "IC302") (pin "15") (pinfunction "AVDD_1_15") (pintype "passive"))
      (node (ref "IC302") (pin "26") (pinfunction "AVDD_2_26") (pintype "passive"))
      (node (ref "IC303") (pin "15") (pinfunction "AVDD_1_15") (pintype "passive"))
      (node (ref "IC303") (pin "26") (pinfunction "AVDD_2_26") (pintype "passive"))
    )
    (net (code "66") (name "AD_AGND") (class "Default")
      (node (ref "C300") (pin "2") (pinfunction "2_2") (pintype "passive"))
      (node (ref "C301") (pin "2") (pinfunction "2_2") (pintype "passive"))
      (node (ref "C302") (pin "2") (pinfunction "2_2") (pintype "passive"))
      (node (ref "C306") (pin "2") (pinfunction "2_2") (pintype "passive"))
      (node (ref "C307") (pin "2") (pinfunction "2_2") (pintype "passive"))
      (node (ref "C308") (pin "2") (pinfunction "2_2") (pintype "passive"))
      (node (ref "C314") (pin "2") (pinfunction "2_2") (pintype "passive"))
      (node (ref "C315") (pin "2") (pinfunction "2_2") (pintype "passive"))
      (node (ref "C317") (pin "2") (pinfunction "2_2") (pintype "passive"))
      (node (ref "C318") (pin "2") (pinfunction "2_2") (pintype "passive"))
      (node (ref "C319") (pin "1") (pinfunction "1_1") (pintype "passive"))
      (node (ref "C321") (pin "1") (pinfunction "1_1") (pintype "passive"))
      (node (ref "C322") (pin "1") (pinfunction "1_1") (pintype "passive"))
      (node (ref "C325") (pin "1") (pinfunction "1_1") (pintype "passive"))
      (node (ref "C328") (pin "2") (pinfunction "2_2") (pintype "passive"))
      (node (ref "C329") (pin "2") (pinfunction "2_2") (pintype "passive"))
      (node (ref "C330") (pin "2") (pinfunction "2_2") (pintype "passive"))
      (node (ref "C334") (pin "2") (pinfunction "2_2") (pintype "passive"))
      (node (ref "C335") (pin "2") (pinfunction "2_2") (pintype "passive"))
      (node (ref "C336") (pin "2") (pinfunction "2_2") (pintype "passive"))
      (node (ref "C342") (pin "2") (pinfunction "2_2") (pintype "passive"))
      (node (ref "C343") (pin "2") (pinfunction "2_2") (pintype "passive"))
      (node (ref "C345") (pin "1") (pinfunction "1_1") (pintype "passive"))
      (node (ref "C346") (pin "2") (pinfunction "2_2") (pintype "passive"))
      (node (ref "C347") (pin "2") (pinfunction "2_2") (pintype "passive"))
      (node (ref "C349") (pin "1") (pinfunction "1_1") (pintype "passive"))
      (node (ref "C350") (pin "1") (pinfunction "1_1") (pintype "passive"))
      (node (ref "C353") (pin "1") (pinfunction "1_1") (pintype "passive"))
      (node (ref "IC300") (pin "16") (pinfunction "AVSS_1_16") (pintype "passive"))
      (node (ref "IC300") (pin "17") (pinfunction "SENSE_17") (pintype "passive"))
      (node (ref "IC300") (pin "19") (pinfunction "REFCOM(AVSS)_19") (pintype "passive"))
      (node (ref "IC300") (pin "25") (pinfunction "AVSS_2_25") (pintype "passive"))
      (node (ref "IC301") (pin "16") (pinfunction "AVSS_1_16") (pintype "passive"))
      (node (ref "IC301") (pin "17") (pinfunction "SENSE_17") (pintype "passive"))
      (node (ref "IC301") (pin "19") (pinfunction "REFCOM(AVSS)_19") (pintype "passive"))
      (node (ref "IC301") (pin "25") (pinfunction "AVSS_2_25") (pintype "passive"))
      (node (ref "IC302") (pin "16") (pinfunction "AVSS_1_16") (pintype "passive"))
      (node (ref "IC302") (pin "17") (pinfunction "SENSE_17") (pintype "passive"))
      (node (ref "IC302") (pin "19") (pinfunction "REFCOM(AVSS)_19") (pintype "passive"))
      (node (ref "IC302") (pin "25") (pinfunction "AVSS_2_25") (pintype "passive"))
      (node (ref "IC303") (pin "16") (pinfunction "AVSS_1_16") (pintype "passive"))
      (node (ref "IC303") (pin "17") (pinfunction "SENSE_17") (pintype "passive"))
      (node (ref "IC303") (pin "19") (pinfunction "REFCOM(AVSS)_19") (pintype "passive"))
      (node (ref "IC303") (pin "25") (pinfunction "AVSS_2_25") (pintype "passive"))
      (node (ref "JP300") (pin "2") (pinfunction "GND_2") (pintype "passive"))
      (node (ref "JP300") (pin "3") (pinfunction "GND_3") (pintype "passive"))
      (node (ref "JP301") (pin "2") (pinfunction "GND_2") (pintype "passive"))
      (node (ref "JP301") (pin "3") (pinfunction "GND_3") (pintype "passive"))
      (node (ref "JP302") (pin "2") (pinfunction "GND_2") (pintype "passive"))
      (node (ref "JP302") (pin "3") (pinfunction "GND_3") (pintype "passive"))
      (node (ref "JP303") (pin "2") (pinfunction "GND_2") (pintype "passive"))
      (node (ref "JP303") (pin "3") (pinfunction "GND_3") (pintype "passive"))
      (node (ref "R300") (pin "1") (pinfunction "1_1") (pintype "passive"))
      (node (ref "R301") (pin "1") (pinfunction "1_1") (pintype "passive"))
      (node (ref "R310") (pin "2") (pinfunction "2_2") (pintype "passive"))
      (node (ref "R313") (pin "2") (pinfunction "2_2") (pintype "passive"))
      (node (ref "R314") (pin "1") (pinfunction "1_1") (pintype "passive"))
      (node (ref "R315") (pin "1") (pinfunction "1_1") (pintype "passive"))
      (node (ref "R316") (pin "1") (pinfunction "1_1") (pintype "passive"))
      (node (ref "R317") (pin "1") (pinfunction "1_1") (pintype "passive"))
      (node (ref "R318") (pin "1") (pinfunction "1_1") (pintype "passive"))
      (node (ref "R319") (pin "1") (pinfunction "1_1") (pintype "passive"))
      (node (ref "R326") (pin "2") (pinfunction "2_2") (pintype "passive"))
      (node (ref "R329") (pin "1") (pinfunction "1_1") (pintype "passive"))
      (node (ref "R330") (pin "1") (pinfunction "1_1") (pintype "passive"))
      (node (ref "R333") (pin "2") (pinfunction "2_2") (pintype "passive"))
      (node (ref "R334") (pin "1") (pinfunction "1_1") (pintype "passive"))
      (node (ref "R335") (pin "1") (pinfunction "1_1") (pintype "passive"))
    )
    (net (code "67") (name "DGND") (class "Default")
      (node (ref "C303") (pin "2") (pinfunction "2_2") (pintype "passive"))
      (node (ref "C304") (pin "2") (pinfunction "2_2") (pintype "passive"))
      (node (ref "C305") (pin "2") (pinfunction "2_2") (pintype "passive"))
      (node (ref "C309") (pin "2") (pinfunction "2_2") (pintype "passive"))
      (node (ref "C310") (pin "2") (pinfunction "2_2") (pintype "passive"))
      (node (ref "C311") (pin "2") (pinfunction "2_2") (pintype "passive"))
      (node (ref "C331") (pin "2") (pinfunction "2_2") (pintype "passive"))
      (node (ref "C332") (pin "2") (pinfunction "2_2") (pintype "passive"))
      (node (ref "C333") (pin "2") (pinfunction "2_2") (pintype "passive"))
      (node (ref "C337") (pin "2") (pinfunction "2_2") (pintype "passive"))
      (node (ref "C338") (pin "2") (pinfunction "2_2") (pintype "passive"))
      (node (ref "C339") (pin "2") (pinfunction "2_2") (pintype "passive"))
      (node (ref "IC300") (pin "27") (pinfunction "DRVSS_27") (pintype "passive"))
      (node (ref "IC301") (pin "27") (pinfunction "DRVSS_27") (pintype "passive"))
      (node (ref "IC302") (pin "27") (pinfunction "DRVSS_27") (pintype "passive"))
      (node (ref "IC303") (pin "27") (pinfunction "DRVSS_27") (pintype "passive"))
      (node (ref "R300") (pin "2") (pinfunction "2_2") (pintype "passive"))
      (node (ref "R301") (pin "2") (pinfunction "2_2") (pintype "passive"))
      (node (ref "R318") (pin "2") (pinfunction "2_2") (pintype "passive"))
      (node (ref "R319") (pin "2") (pinfunction "2_2") (pintype "passive"))
    )
    (net (code "68") (name "Net-(C314-Pad1)") (class "Default")
      (node (ref "C314") (pin "1") (pinfunction "1_1") (pintype "passive"))
      (node (ref "C315") (pin "1") (pinfunction "1_1") (pintype "passive"))
      (node (ref "R304") (pin "2") (pinfunction "2_2") (pintype "passive"))
    )
    (net (code "69") (name "Net-(C316-Pad1)") (class "Default")
      (node (ref "C316") (pin "1") (pinfunction "1_1") (pintype "passive"))
      (node (ref "R305") (pin "2") (pinfunction "2_2") (pintype "passive"))
      (node (ref "R314") (pin "2") (pinfunction "2_2") (pintype "passive"))
    )
    (net (code "70") (name "Net-(C316-Pad2)") (class "Default")
      (node (ref "C316") (pin "2") (pinfunction "2_2") (pintype "passive"))
      (node (ref "R306") (pin "2") (pinfunction "2_2") (pintype "passive"))
    )
    (net (code "71") (name "Net-(C317-Pad1)") (class "Default")
      (node (ref "C317") (pin "1") (pinfunction "1_1") (pintype "passive"))
      (node (ref "C318") (pin "1") (pinfunction "1_1") (pintype "passive"))
      (node (ref "R308") (pin "2") (pinfunction "2_2") (pintype "passive"))
    )
    (net (code "72") (name "Net-(C320-Pad1)") (class "Default")
      (node (ref "C320") (pin "1") (pinfunction "1_1") (pintype "passive"))
      (node (ref "R309") (pin "2") (pinfunction "2_2") (pintype "passive"))
      (node (ref "R316") (pin "2") (pinfunction "2_2") (pintype "passive"))
    )
    (net (code "73") (name "Net-(C320-Pad2)") (class "Default")
      (node (ref "C320") (pin "2") (pinfunction "2_2") (pintype "passive"))
      (node (ref "R311") (pin "2") (pinfunction "2_2") (pintype "passive"))
    )
    (net (code "74") (name "Net-(C342-Pad1)") (class "Default")
      (node (ref "C342") (pin "1") (pinfunction "1_1") (pintype "passive"))
      (node (ref "C343") (pin "1") (pinfunction "1_1") (pintype "passive"))
      (node (ref "R322") (pin "2") (pinfunction "2_2") (pintype "passive"))
    )
    (net (code "75") (name "Net-(C344-Pad1)") (class "Default")
      (node (ref "C344") (pin "1") (pinfunction "1_1") (pintype "passive"))
      (node (ref "R323") (pin "2") (pinfunction "2_2") (pintype "passive"))
      (node (ref "R329") (pin "2") (pinfunction "2_2") (pintype "passive"))
    )
    (net (code "76") (name "Net-(C344-Pad2)") (class "Default")
      (node (ref "C344") (pin "2") (pinfunction "2_2") (pintype "passive"))
      (node (ref "R324") (pin "2") (pinfunction "2_2") (pintype "passive"))
    )
    (net (code "77") (name "Net-(C346-Pad1)") (class "Default")
      (node (ref "C346") (pin "1") (pinfunction "1_1") (pintype "passive"))
      (node (ref "C347") (pin "1") (pinfunction "1_1") (pintype "passive"))
      (node (ref "R327") (pin "2") (pinfunction "2_2") (pintype "passive"))
    )
    (net (code "78") (name "Net-(C348-Pad1)") (class "Default")
      (node (ref "C348") (pin "1") (pinfunction "1_1") (pintype "passive"))
      (node (ref "R328") (pin "2") (pinfunction "2_2") (pintype "passive"))
      (node (ref "R334") (pin "2") (pinfunction "2_2") (pintype "passive"))
    )
    (net (code "79") (name "Net-(C348-Pad2)") (class "Default")
      (node (ref "C348") (pin "2") (pinfunction "2_2") (pintype "passive"))
      (node (ref "R331") (pin "2") (pinfunction "2_2") (pintype "passive"))
    )
    (net (code "80") (name "Net-(IC300-CAPB)") (class "Default")
      (node (ref "C322") (pin "2") (pinfunction "2_2") (pintype "passive"))
      (node (ref "C323") (pin "1") (pinfunction "1_1") (pintype "passive"))
      (node (ref "C324") (pin "1") (pinfunction "1_1") (pintype "passive"))
      (node (ref "IC300") (pin "20") (pinfunction "CAPB_20") (pintype "passive"))
    )
    (net (code "81") (name "Net-(IC300-CAPT)") (class "Default")
      (node (ref "C319") (pin "2") (pinfunction "2_2") (pintype "passive"))
      (node (ref "C323") (pin "2") (pinfunction "2_2") (pintype "passive"))
      (node (ref "C324") (pin "2") (pinfunction "2_2") (pintype "passive"))
      (node (ref "IC300") (pin "21") (pinfunction "CAPT_21") (pintype "passive"))
    )
    (net (code "82") (name "Net-(IC300-CLK)") (class "Default")
      (node (ref "C312") (pin "1") (pinfunction "1_1") (pintype "passive"))
      (node (ref "IC300") (pin "1") (pinfunction "CLK_1") (pintype "passive"))
      (node (ref "R302") (pin "2") (pinfunction "2_2") (pintype "passive"))
    )
    (net (code "83") (name "Net-(IC300-MODE)") (class "Default")
      (node (ref "IC300") (pin "22") (pinfunction "MODE_22") (pintype "passive"))
      (node (ref "R310") (pin "1") (pinfunction "1_1") (pintype "passive"))
    )
    (net (code "84") (name "Net-(IC300-VINA)") (class "Default")
      (node (ref "IC300") (pin "23") (pinfunction "VINA_23") (pintype "passive"))
      (node (ref "R306") (pin "1") (pinfunction "1_1") (pintype "passive"))
    )
    (net (code "85") (name "Net-(IC300-VINB)") (class "Default")
      (node (ref "IC300") (pin "24") (pinfunction "VINB_24") (pintype "passive"))
      (node (ref "R304") (pin "1") (pinfunction "1_1") (pintype "passive"))
    )
    (net (code "86") (name "Net-(IC301-CAPB)") (class "Default")
      (node (ref "C325") (pin "2") (pinfunction "2_2") (pintype "passive"))
      (node (ref "C326") (pin "1") (pinfunction "1_1") (pintype "passive"))
      (node (ref "C327") (pin "1") (pinfunction "1_1") (pintype "passive"))
      (node (ref "IC301") (pin "20") (pinfunction "CAPB_20") (pintype "passive"))
    )
    (net (code "87") (name "Net-(IC301-CAPT)") (class "Default")
      (node (ref "C321") (pin "2") (pinfunction "2_2") (pintype "passive"))
      (node (ref "C326") (pin "2") (pinfunction "2_2") (pintype "passive"))
      (node (ref "C327") (pin "2") (pinfunction "2_2") (pintype "passive"))
      (node (ref "IC301") (pin "21") (pinfunction "CAPT_21") (pintype "passive"))
    )
    (net (code "88") (name "Net-(IC301-CLK)") (class "Default")
      (node (ref "C313") (pin "1") (pinfunction "1_1") (pintype "passive"))
      (node (ref "IC301") (pin "1") (pinfunction "CLK_1") (pintype "passive"))
      (node (ref "R303") (pin "2") (pinfunction "2_2") (pintype "passive"))
    )
    (net (code "89") (name "Net-(IC301-MODE)") (class "Default")
      (node (ref "IC301") (pin "22") (pinfunction "MODE_22") (pintype "passive"))
      (node (ref "R313") (pin "1") (pinfunction "1_1") (pintype "passive"))
    )
    (net (code "90") (name "Net-(IC301-VINA)") (class "Default")
      (node (ref "IC301") (pin "23") (pinfunction "VINA_23") (pintype "passive"))
      (node (ref "R311") (pin "1") (pinfunction "1_1") (pintype "passive"))
    )
    (net (code "91") (name "Net-(IC301-VINB)") (class "Default")
      (node (ref "IC301") (pin "24") (pinfunction "VINB_24") (pintype "passive"))
      (node (ref "R308") (pin "1") (pinfunction "1_1") (pintype "passive"))
    )
    (net (code "92") (name "Net-(IC302-CAPB)") (class "Default")
      (node (ref "C349") (pin "2") (pinfunction "2_2") (pintype "passive"))
      (node (ref "C351") (pin "1") (pinfunction "1_1") (pintype "passive"))
      (node (ref "C352") (pin "1") (pinfunction "1_1") (pintype "passive"))
      (node (ref "IC302") (pin "20") (pinfunction "CAPB_20") (pintype "passive"))
    )
    (net (code "93") (name "Net-(IC302-CAPT)") (class "Default")
      (node (ref "C345") (pin "2") (pinfunction "2_2") (pintype "passive"))
      (node (ref "C351") (pin "2") (pinfunction "2_2") (pintype "passive"))
      (node (ref "C352") (pin "2") (pinfunction "2_2") (pintype "passive"))
      (node (ref "IC302") (pin "21") (pinfunction "CAPT_21") (pintype "passive"))
    )
    (net (code "94") (name "Net-(IC302-CLK)") (class "Default")
      (node (ref "C340") (pin "1") (pinfunction "1_1") (pintype "passive"))
      (node (ref "IC302") (pin "1") (pinfunction "CLK_1") (pintype "passive"))
      (node (ref "R320") (pin "2") (pinfunction "2_2") (pintype "passive"))
    )
    (net (code "95") (name "Net-(IC302-MODE)") (class "Default")
      (node (ref "IC302") (pin "22") (pinfunction "MODE_22") (pintype "passive"))
      (node (ref "R326") (pin "1") (pinfunction "1_1") (pintype "passive"))
    )
    (net (code "96") (name "Net-(IC302-VINA)") (class "Default")
      (node (ref "IC302") (pin "23") (pinfunction "VINA_23") (pintype "passive"))
      (node (ref "R324") (pin "1") (pinfunction "1_1") (pintype "passive"))
    )
    (net (code "97") (name "Net-(IC302-VINB)") (class "Default")
      (node (ref "IC302") (pin "24") (pinfunction "VINB_24") (pintype "passive"))
      (node (ref "R322") (pin "1") (pinfunction "1_1") (pintype "passive"))
    )
    (net (code "98") (name "Net-(IC303-CAPB)") (class "Default")
      (node (ref "C353") (pin "2") (pinfunction "2_2") (pintype "passive"))
      (node (ref "C354") (pin "1") (pinfunction "1_1") (pintype "passive"))
      (node (ref "C355") (pin "1") (pinfunction "1_1") (pintype "passive"))
      (node (ref "IC303") (pin "20") (pinfunction "CAPB_20") (pintype "passive"))
    )
    (net (code "99") (name "Net-(IC303-CAPT)") (class "Default")
      (node (ref "C350") (pin "2") (pinfunction "2_2") (pintype "passive"))
      (node (ref "C354") (pin "2") (pinfunction "2_2") (pintype "passive"))
      (node (ref "C355") (pin "2") (pinfunction "2_2") (pintype "passive"))
      (node (ref "IC303") (pin "21") (pinfunction "CAPT_21") (pintype "passive"))
    )
    (net (code "100") (name "Net-(IC303-CLK)") (class "Default")
      (node (ref "C341") (pin "1") (pinfunction "1_1") (pintype "passive"))
      (node (ref "IC303") (pin "1") (pinfunction "CLK_1") (pintype "passive"))
      (node (ref "R321") (pin "2") (pinfunction "2_2") (pintype "passive"))
    )
    (net (code "101") (name "Net-(IC303-MODE)") (class "Default")
      (node (ref "IC303") (pin "22") (pinfunction "MODE_22") (pintype "passive"))
      (node (ref "R333") (pin "1") (pinfunction "1_1") (pintype "passive"))
    )
    (net (code "102") (name "Net-(IC303-VINA)") (class "Default")
      (node (ref "IC303") (pin "23") (pinfunction "VINA_23") (pintype "passive"))
      (node (ref "R331") (pin "1") (pinfunction "1_1") (pintype "passive"))
    )
    (net (code "103") (name "Net-(IC303-VINB)") (class "Default")
      (node (ref "IC303") (pin "24") (pinfunction "VINB_24") (pintype "passive"))
      (node (ref "R327") (pin "1") (pinfunction "1_1") (pintype "passive"))
    )
    (net (code "104") (name "Net-(JP300-ANT)") (class "Default")
      (node (ref "JP300") (pin "1") (pinfunction "ANT_1") (pintype "passive"))
      (node (ref "R307") (pin "2") (pinfunction "2_2") (pintype "passive"))
    )
    (net (code "105") (name "Net-(JP301-ANT)") (class "Default")
      (node (ref "JP301") (pin "1") (pinfunction "ANT_1") (pintype "passive"))
      (node (ref "R312") (pin "2") (pinfunction "2_2") (pintype "passive"))
    )
    (net (code "106") (name "Net-(JP302-ANT)") (class "Default")
      (node (ref "JP302") (pin "1") (pinfunction "ANT_1") (pintype "passive"))
      (node (ref "R325") (pin "2") (pinfunction "2_2") (pintype "passive"))
    )
    (net (code "107") (name "Net-(JP303-ANT)") (class "Default")
      (node (ref "JP303") (pin "1") (pinfunction "ANT_1") (pintype "passive"))
      (node (ref "R332") (pin "2") (pinfunction "2_2") (pintype "passive"))
    )
    (net (code "108") (name "Net-(R305-Pad1)") (class "Default")
      (node (ref "R305") (pin "1") (pinfunction "1_1") (pintype "passive"))
      (node (ref "R307") (pin "1") (pinfunction "1_1") (pintype "passive"))
      (node (ref "R315") (pin "2") (pinfunction "2_2") (pintype "passive"))
    )
    (net (code "109") (name "Net-(R309-Pad1)") (class "Default")
      (node (ref "R309") (pin "1") (pinfunction "1_1") (pintype "passive"))
      (node (ref "R312") (pin "1") (pinfunction "1_1") (pintype "passive"))
      (node (ref "R317") (pin "2") (pinfunction "2_2") (pintype "passive"))
    )
    (net (code "110") (name "Net-(R323-Pad1)") (class "Default")
      (node (ref "R323") (pin "1") (pinfunction "1_1") (pintype "passive"))
      (node (ref "R325") (pin "1") (pinfunction "1_1") (pintype "passive"))
      (node (ref "R330") (pin "2") (pinfunction "2_2") (pintype "passive"))
    )
    (net (code "111") (name "Net-(R328-Pad1)") (class "Default")
      (node (ref "R328") (pin "1") (pinfunction "1_1") (pintype "passive"))
      (node (ref "R332") (pin "1") (pinfunction "1_1") (pintype "passive"))
      (node (ref "R335") (pin "2") (pinfunction "2_2") (pintype "passive"))
    )
    (net (code "112") (name "VCC3V3") (class "Default")
      (node (ref "C303") (pin "1") (pinfunction "1_1") (pintype "passive"))
      (node (ref "C304") (pin "1") (pinfunction "1_1") (pintype "passive"))
      (node (ref "C305") (pin "1") (pinfunction "1_1") (pintype "passive"))
      (node (ref "C309") (pin "1") (pinfunction "1_1") (pintype "passive"))
      (node (ref "C310") (pin "1") (pinfunction "1_1") (pintype "passive"))
      (node (ref "C311") (pin "1") (pinfunction "1_1") (pintype "passive"))
      (node (ref "C331") (pin "1") (pinfunction "1_1") (pintype "passive"))
      (node (ref "C332") (pin "1") (pinfunction "1_1") (pintype "passive"))
      (node (ref "C333") (pin "1") (pinfunction "1_1") (pintype "passive"))
      (node (ref "C337") (pin "1") (pinfunction "1_1") (pintype "passive"))
      (node (ref "C338") (pin "1") (pinfunction "1_1") (pintype "passive"))
      (node (ref "C339") (pin "1") (pinfunction "1_1") (pintype "passive"))
      (node (ref "IC300") (pin "28") (pinfunction "DRVDD_28") (pintype "passive"))
      (node (ref "IC301") (pin "28") (pinfunction "DRVDD_28") (pintype "passive"))
      (node (ref "IC302") (pin "28") (pinfunction "DRVDD_28") (pintype "passive"))
      (node (ref "IC303") (pin "28") (pinfunction "DRVDD_28") (pintype "passive"))
      (node (ref "R302") (pin "1") (pinfunction "1_1") (pintype "passive"))
      (node (ref "R303") (pin "1") (pinfunction "1_1") (pintype "passive"))
      (node (ref "R320") (pin "1") (pinfunction "1_1") (pintype "passive"))
      (node (ref "R321") (pin "1") (pinfunction "1_1") (pintype "passive"))
    )
    (net (code "113") (name "unconnected-(IC300-VREF-Pad18)") (class "Default")
      (node (ref "IC300") (pin "18") (pinfunction "VREF_18") (pintype "passive"))
    )
    (net (code "114") (name "unconnected-(IC301-VREF-Pad18)") (class "Default")
      (node (ref "IC301") (pin "18") (pinfunction "VREF_18") (pintype "passive"))
    )
    (net (code "115") (name "unconnected-(IC302-VREF-Pad18)") (class "Default")
      (node (ref "IC302") (pin "18") (pinfunction "VREF_18") (pintype "passive"))
    )
    (net (code "116") (name "unconnected-(IC303-VREF-Pad18)") (class "Default")
      (node (ref "IC303") (pin "18") (pinfunction "VREF_18") (pintype "passive"))
    )
  )
)
